# 3_-_Periphery.net
KiCad netlist of a schematic drawn in Altium Designer
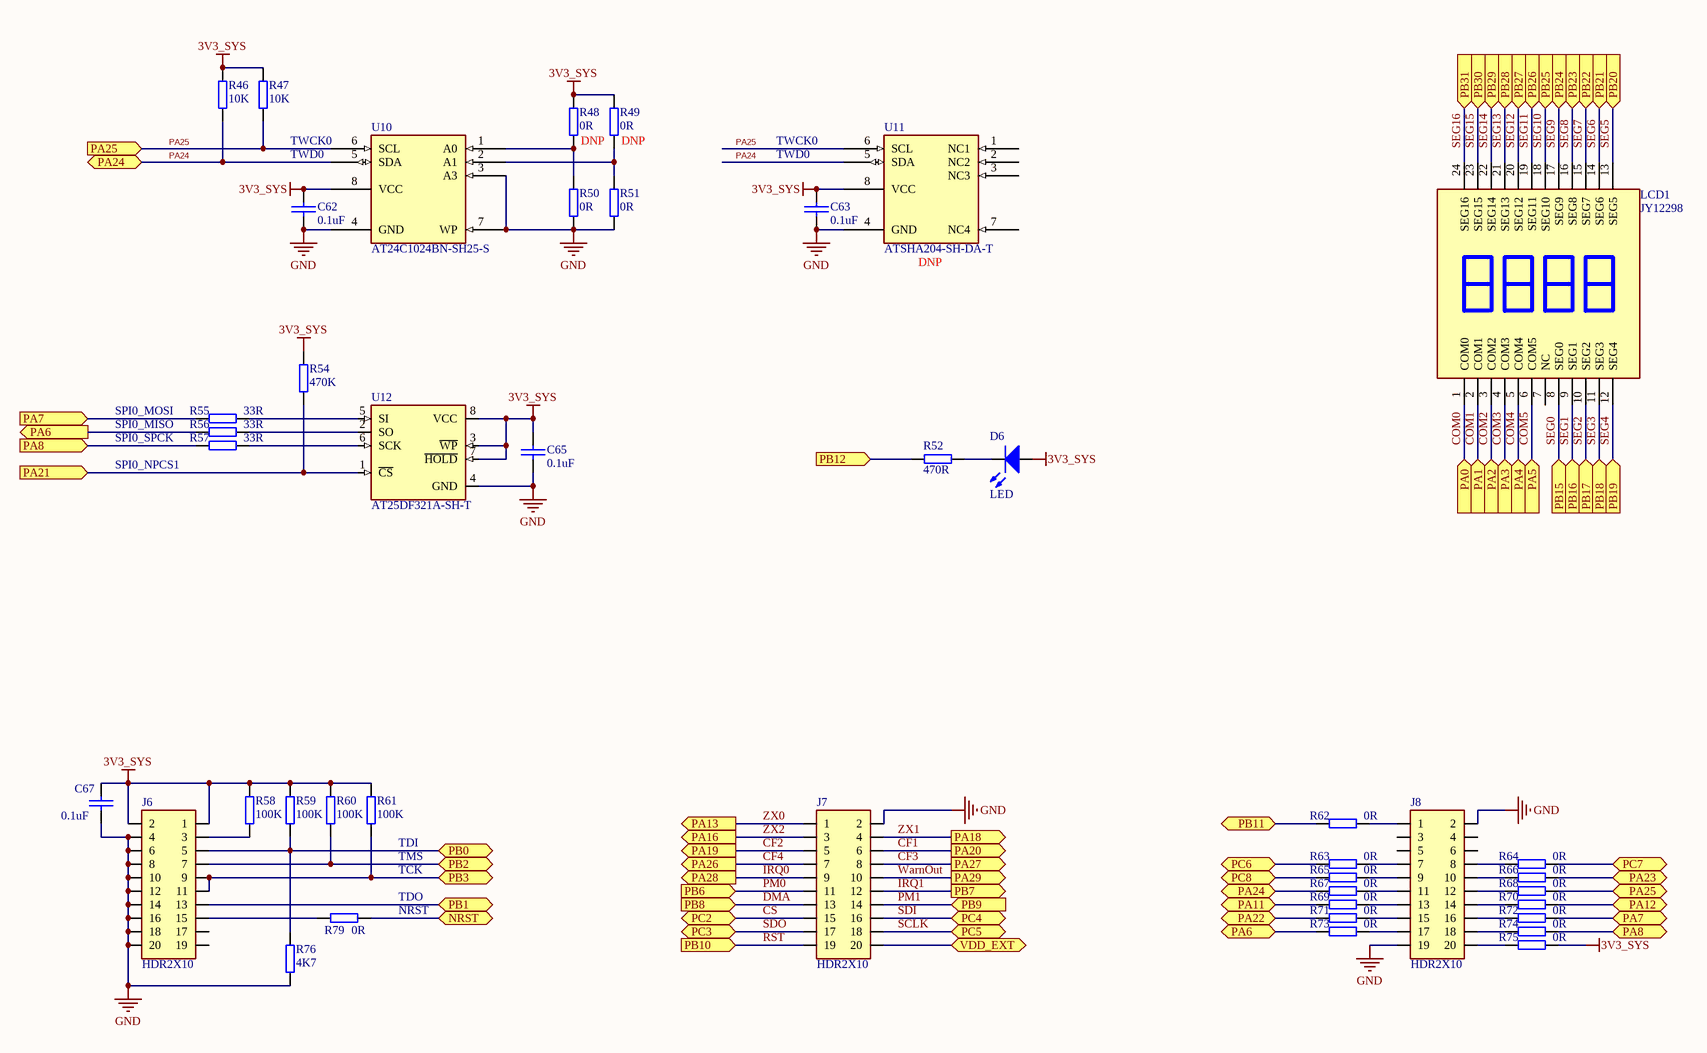
[diagram p0: 3 - Periphery.SchDoc]

(export (version "E")
  (design (tool "Eeschema 10.0.6"))
  (components
    (comp (ref "C62") (value "0.1uF") (footprint "C0603") (libsource (lib "SchLib(AD10)") (part "CAP")))
    (comp (ref "C63") (value "0.1uF") (footprint "C0603") (libsource (lib "SchLib(AD10)") (part "CAP")))
    (comp (ref "C65") (value "0.1uF") (footprint "C0603") (libsource (lib "SchLib(AD10)") (part "CAP")))
    (comp (ref "C67") (value "0.1uF") (footprint "C0603") (libsource (lib "SchLib(AD10)") (part "CAP")))
    (comp (ref "D6") (value "LED") (footprint "LED-0805G") (libsource (lib "SchLib(AD10)") (part "LED")))
    (comp (ref "J6") (value "HDR2X10") (footprint "HDR2X10") (libsource (lib "") (part "HDR2X10_1")))
    (comp (ref "J7")
      (value "HDR2X10")
      (footprint "HDR2X10")
      (libsource (lib "SchLib(AD10)") (part "HDR2X10"))
    )
    (comp (ref "J8")
      (value "HDR2X10")
      (footprint "HDR2X10")
      (libsource (lib "SchLib(AD10)") (part "HDR2X10"))
    )
    (comp (ref "LCD1")
      (value "JY12298")
      (footprint "LCD_JY12298")
      (description "Display,FSTN,Positive,Reflective,JY12298,60.15x45.1mm")
      (fields (field (name "MANUFACTURER") "翼雅"))
      (libsource (lib "SchLib(AD10)") (part "LCD_JY12298"))
    )
    (comp (ref "R46") (value "10K") (footprint "R0603") (libsource (lib "SchLib(AD10)") (part "RES")))
    (comp (ref "R47") (value "10K") (footprint "R0603") (libsource (lib "SchLib(AD10)") (part "RES")))
    (comp (ref "R48") (value "0R") (footprint "R0603") (libsource (lib "SchLib(AD10)") (part "RES")))
    (comp (ref "R49") (value "0R") (footprint "R0603") (libsource (lib "SchLib(AD10)") (part "RES")))
    (comp (ref "R50") (value "0R") (footprint "R0603") (libsource (lib "SchLib(AD10)") (part "RES")))
    (comp (ref "R51") (value "0R") (footprint "R0603") (libsource (lib "SchLib(AD10)") (part "RES")))
    (comp (ref "R52") (value "470R") (footprint "R0603") (libsource (lib "SchLib(AD10)") (part "RES")))
    (comp (ref "R54") (value "470K") (footprint "R0603") (libsource (lib "SchLib(AD10)") (part "RES")))
    (comp (ref "R55") (value "33R") (footprint "R0603") (libsource (lib "SchLib(AD10)") (part "RES")))
    (comp (ref "R56") (value "33R") (footprint "R0603") (libsource (lib "SchLib(AD10)") (part "RES")))
    (comp (ref "R57") (value "33R") (footprint "R0603") (libsource (lib "SchLib(AD10)") (part "RES")))
    (comp (ref "R58") (value "100K") (footprint "R0603") (libsource (lib "SchLib(AD10)") (part "RES")))
    (comp (ref "R59") (value "100K") (footprint "R0603") (libsource (lib "SchLib(AD10)") (part "RES")))
    (comp (ref "R60") (value "100K") (footprint "R0603") (libsource (lib "SchLib(AD10)") (part "RES")))
    (comp (ref "R61") (value "100K") (footprint "R0603") (libsource (lib "SchLib(AD10)") (part "RES")))
    (comp (ref "R62") (value "0R") (footprint "R0603") (libsource (lib "SchLib(AD10)") (part "RES")))
    (comp (ref "R63") (value "0R") (footprint "R0603") (libsource (lib "SchLib(AD10)") (part "RES")))
    (comp (ref "R64") (value "0R") (footprint "R0603") (libsource (lib "SchLib(AD10)") (part "RES")))
    (comp (ref "R65") (value "0R") (footprint "R0603") (libsource (lib "SchLib(AD10)") (part "RES")))
    (comp (ref "R66") (value "0R") (footprint "R0603") (libsource (lib "SchLib(AD10)") (part "RES")))
    (comp (ref "R67") (value "0R") (footprint "R0603") (libsource (lib "SchLib(AD10)") (part "RES")))
    (comp (ref "R68") (value "0R") (footprint "R0603") (libsource (lib "SchLib(AD10)") (part "RES")))
    (comp (ref "R69") (value "0R") (footprint "R0603") (libsource (lib "SchLib(AD10)") (part "RES")))
    (comp (ref "R70") (value "0R") (footprint "R0603") (libsource (lib "SchLib(AD10)") (part "RES")))
    (comp (ref "R71") (value "0R") (footprint "R0603") (libsource (lib "SchLib(AD10)") (part "RES")))
    (comp (ref "R72") (value "0R") (footprint "R0603") (libsource (lib "SchLib(AD10)") (part "RES")))
    (comp (ref "R73") (value "0R") (footprint "R0603") (libsource (lib "SchLib(AD10)") (part "RES")))
    (comp (ref "R74") (value "0R") (footprint "R0603") (libsource (lib "SchLib(AD10)") (part "RES")))
    (comp (ref "R75") (value "0R") (footprint "R0603") (libsource (lib "SchLib(AD10)") (part "RES")))
    (comp (ref "R76") (value "4K7") (footprint "R0603") (libsource (lib "SchLib(AD10)") (part "RES")))
    (comp (ref "R79") (value "0R") (footprint "R0603") (libsource (lib "SchLib(AD10)") (part "RES")))
    (comp (ref "U10")
      (value "AT24C1024BN-SH25-S")
      (footprint "SO8")
      (description "Two Wires Serial EEPROM")
      (fields
        (field (name "MANUFACTURER") "Atmel")
        (field (name "MANUFACTURER PART NUMBER") "AT24C1024BN-SH25")
      )
      (libsource (lib "SchLib(AD10)") (part "AT24C512BN-SH25-SO8_1"))
    )
    (comp (ref "U11")
      (value "ATSHA204-SH-DA-T")
      (footprint "SO8")
      (description "IC,CryptoAuthentication,ATSHA204-SH-DA-T")
      (fields (field (name "MANUFACTURER") "ATMEL"))
      (libsource (lib "SchLib(AD10)") (part "ATSHA204-SH-DA-T"))
    )
    (comp (ref "U12")
      (value "AT25DF321A-SH-T")
      (footprint "SOIC8")
      (description "32 Mb Serial DataFlash")
      (fields (field (name "MANUFACTURER") "ATMEL"))
      (libsource (lib "SchLib(AD10)") (part "AT25DF321_SU"))
    )
  )
  (nets
    (net (code "1") (name "/CF1") (class "Default")
      (node (ref "J7") (pin "6") (pinfunction "6_6") (pintype "passive"))
    )
    (net (code "2") (name "/CF2") (class "Default")
      (node (ref "J7") (pin "5") (pinfunction "5_5") (pintype "passive"))
    )
    (net (code "3") (name "/CF3") (class "Default")
      (node (ref "J7") (pin "8") (pinfunction "8_8") (pintype "passive"))
    )
    (net (code "4") (name "/CF4") (class "Default")
      (node (ref "J7") (pin "7") (pinfunction "7_7") (pintype "passive"))
    )
    (net (code "5") (name "/COM0") (class "Default")
      (node (ref "LCD1") (pin "1") (pinfunction "COM0_1") (pintype "passive"))
    )
    (net (code "6") (name "/COM1") (class "Default")
      (node (ref "LCD1") (pin "2") (pinfunction "COM1_2") (pintype "passive"))
    )
    (net (code "7") (name "/COM2") (class "Default")
      (node (ref "LCD1") (pin "3") (pinfunction "COM2_3") (pintype "passive"))
    )
    (net (code "8") (name "/COM3") (class "Default")
      (node (ref "LCD1") (pin "4") (pinfunction "COM3_4") (pintype "passive"))
    )
    (net (code "9") (name "/COM4") (class "Default")
      (node (ref "LCD1") (pin "5") (pinfunction "COM4_5") (pintype "passive"))
    )
    (net (code "10") (name "/COM5") (class "Default")
      (node (ref "LCD1") (pin "6") (pinfunction "COM5_6") (pintype "passive"))
    )
    (net (code "11") (name "/CS") (class "Default")
      (node (ref "J7") (pin "15") (pinfunction "15_15") (pintype "passive"))
    )
    (net (code "12") (name "/DMA") (class "Default")
      (node (ref "J7") (pin "13") (pinfunction "13_13") (pintype "passive"))
    )
    (net (code "13") (name "/IRQ0") (class "Default")
      (node (ref "J7") (pin "9") (pinfunction "9_9") (pintype "passive"))
    )
    (net (code "14") (name "/IRQ1") (class "Default")
      (node (ref "J7") (pin "12") (pinfunction "12_12") (pintype "passive"))
    )
    (net (code "15") (name "/NRST") (class "Default")
      (node (ref "R79") (pin "2") (pinfunction "2_2") (pintype "passive"))
    )
    (net (code "16") (name "/PA6") (class "Default")
      (node (ref "R56") (pin "1") (pinfunction "1_1") (pintype "passive"))
      (node (ref "R73") (pin "1") (pinfunction "1_1") (pintype "passive"))
    )
    (net (code "17") (name "/PA7") (class "Default")
      (node (ref "R55") (pin "1") (pinfunction "1_1") (pintype "passive"))
      (node (ref "R72") (pin "2") (pinfunction "2_2") (pintype "passive"))
    )
    (net (code "18") (name "/PA8") (class "Default")
      (node (ref "R57") (pin "1") (pinfunction "1_1") (pintype "passive"))
      (node (ref "R74") (pin "2") (pinfunction "2_2") (pintype "passive"))
    )
    (net (code "19") (name "/PA11") (class "Default")
      (node (ref "R69") (pin "1") (pinfunction "1_1") (pintype "passive"))
    )
    (net (code "20") (name "/PA12") (class "Default")
      (node (ref "R70") (pin "2") (pinfunction "2_2") (pintype "passive"))
    )
    (net (code "21") (name "/PA21") (class "Default")
      (node (ref "R54") (pin "1") (pinfunction "1_1") (pintype "passive"))
      (node (ref "U12") (pin "1") (pinfunction "~{CS}_1") (pintype "input"))
    )
    (net (code "22") (name "/PA22") (class "Default")
      (node (ref "R71") (pin "1") (pinfunction "1_1") (pintype "passive"))
    )
    (net (code "23") (name "/PA23") (class "Default")
      (node (ref "R66") (pin "2") (pinfunction "2_2") (pintype "passive"))
    )
    (net (code "24") (name "/PA24") (class "Default")
      (node (ref "R46") (pin "1") (pinfunction "1_1") (pintype "passive"))
      (node (ref "R67") (pin "1") (pinfunction "1_1") (pintype "passive"))
      (node (ref "U10") (pin "5") (pinfunction "SDA_5") (pintype "bidirectional"))
      (node (ref "U11") (pin "5") (pinfunction "SDA_5") (pintype "bidirectional"))
    )
    (net (code "25") (name "/PA25") (class "Default")
      (node (ref "R47") (pin "1") (pinfunction "1_1") (pintype "passive"))
      (node (ref "R68") (pin "2") (pinfunction "2_2") (pintype "passive"))
      (node (ref "U10") (pin "6") (pinfunction "SCL_6") (pintype "input"))
      (node (ref "U11") (pin "6") (pinfunction "SCL_6") (pintype "input"))
    )
    (net (code "26") (name "/PB0") (class "Default")
      (node (ref "J6") (pin "5") (pinfunction "5_5") (pintype "passive"))
      (node (ref "R59") (pin "1") (pinfunction "1_1") (pintype "passive"))
      (node (ref "R76") (pin "2") (pinfunction "2_2") (pintype "passive"))
    )
    (net (code "27") (name "/PB1") (class "Default")
      (node (ref "J6") (pin "13") (pinfunction "13_13") (pintype "passive"))
    )
    (net (code "28") (name "/PB2") (class "Default")
      (node (ref "J6") (pin "7") (pinfunction "7_7") (pintype "passive"))
      (node (ref "R60") (pin "1") (pinfunction "1_1") (pintype "passive"))
    )
    (net (code "29") (name "/PB3") (class "Default")
      (node (ref "J6") (pin "11") (pinfunction "11_11") (pintype "passive"))
      (node (ref "J6") (pin "9") (pinfunction "9_9") (pintype "passive"))
      (node (ref "R61") (pin "1") (pinfunction "1_1") (pintype "passive"))
    )
    (net (code "30") (name "/PB11") (class "Default")
      (node (ref "R62") (pin "1") (pinfunction "1_1") (pintype "passive"))
    )
    (net (code "31") (name "/PB12") (class "Default")
      (node (ref "R52") (pin "1") (pinfunction "1_1") (pintype "passive"))
    )
    (net (code "32") (name "/PC6") (class "Default")
      (node (ref "R63") (pin "1") (pinfunction "1_1") (pintype "passive"))
    )
    (net (code "33") (name "/PC7") (class "Default")
      (node (ref "R64") (pin "2") (pinfunction "2_2") (pintype "passive"))
    )
    (net (code "34") (name "/PC8") (class "Default")
      (node (ref "R65") (pin "1") (pinfunction "1_1") (pintype "passive"))
    )
    (net (code "35") (name "/PM0") (class "Default")
      (node (ref "J7") (pin "11") (pinfunction "11_11") (pintype "passive"))
    )
    (net (code "36") (name "/PM1") (class "Default")
      (node (ref "J7") (pin "14") (pinfunction "14_14") (pintype "passive"))
    )
    (net (code "37") (name "/RST") (class "Default")
      (node (ref "J7") (pin "19") (pinfunction "19_19") (pintype "passive"))
    )
    (net (code "38") (name "/SCLK") (class "Default")
      (node (ref "J7") (pin "18") (pinfunction "18_18") (pintype "passive"))
    )
    (net (code "39") (name "/SDI") (class "Default")
      (node (ref "J7") (pin "16") (pinfunction "16_16") (pintype "passive"))
    )
    (net (code "40") (name "/SDO") (class "Default")
      (node (ref "J7") (pin "17") (pinfunction "17_17") (pintype "passive"))
    )
    (net (code "41") (name "/SEG0") (class "Default")
      (node (ref "LCD1") (pin "8") (pinfunction "SEG0_8") (pintype "passive"))
    )
    (net (code "42") (name "/SEG1") (class "Default")
      (node (ref "LCD1") (pin "9") (pinfunction "SEG1_9") (pintype "passive"))
    )
    (net (code "43") (name "/SEG2") (class "Default")
      (node (ref "LCD1") (pin "10") (pinfunction "SEG2_10") (pintype "passive"))
    )
    (net (code "44") (name "/SEG3") (class "Default")
      (node (ref "LCD1") (pin "11") (pinfunction "SEG3_11") (pintype "passive"))
    )
    (net (code "45") (name "/SEG4") (class "Default")
      (node (ref "LCD1") (pin "12") (pinfunction "SEG4_12") (pintype "passive"))
    )
    (net (code "46") (name "/SEG5") (class "Default")
      (node (ref "LCD1") (pin "13") (pinfunction "SEG5_13") (pintype "passive"))
    )
    (net (code "47") (name "/SEG6") (class "Default")
      (node (ref "LCD1") (pin "14") (pinfunction "SEG6_14") (pintype "passive"))
    )
    (net (code "48") (name "/SEG7") (class "Default")
      (node (ref "LCD1") (pin "15") (pinfunction "SEG7_15") (pintype "passive"))
    )
    (net (code "49") (name "/SEG8") (class "Default")
      (node (ref "LCD1") (pin "16") (pinfunction "SEG8_16") (pintype "passive"))
    )
    (net (code "50") (name "/SEG9") (class "Default")
      (node (ref "LCD1") (pin "17") (pinfunction "SEG9_17") (pintype "passive"))
    )
    (net (code "51") (name "/SEG10") (class "Default")
      (node (ref "LCD1") (pin "18") (pinfunction "SEG10_18") (pintype "passive"))
    )
    (net (code "52") (name "/SEG11") (class "Default")
      (node (ref "LCD1") (pin "19") (pinfunction "SEG11_19") (pintype "passive"))
    )
    (net (code "53") (name "/SEG12") (class "Default")
      (node (ref "LCD1") (pin "20") (pinfunction "SEG12_20") (pintype "passive"))
    )
    (net (code "54") (name "/SEG13") (class "Default")
      (node (ref "LCD1") (pin "21") (pinfunction "SEG13_21") (pintype "passive"))
    )
    (net (code "55") (name "/SEG14") (class "Default")
      (node (ref "LCD1") (pin "22") (pinfunction "SEG14_22") (pintype "passive"))
    )
    (net (code "56") (name "/SEG15") (class "Default")
      (node (ref "LCD1") (pin "23") (pinfunction "SEG15_23") (pintype "passive"))
    )
    (net (code "57") (name "/SEG16") (class "Default")
      (node (ref "LCD1") (pin "24") (pinfunction "SEG16_24") (pintype "passive"))
    )
    (net (code "58") (name "/VDD_EXT") (class "Default")
      (node (ref "J7") (pin "20") (pinfunction "20_20") (pintype "passive"))
    )
    (net (code "59") (name "/WarnOut") (class "Default")
      (node (ref "J7") (pin "10") (pinfunction "10_10") (pintype "passive"))
    )
    (net (code "60") (name "/ZX0") (class "Default")
      (node (ref "J7") (pin "1") (pinfunction "1_1") (pintype "passive"))
    )
    (net (code "61") (name "/ZX1") (class "Default")
      (node (ref "J7") (pin "4") (pinfunction "4_4") (pintype "passive"))
    )
    (net (code "62") (name "/ZX2") (class "Default")
      (node (ref "J7") (pin "3") (pinfunction "3_3") (pintype "passive"))
    )
    (net (code "63") (name "3V3_SYS") (class "Default")
      (node (ref "C62") (pin "2") (pintype "passive"))
      (node (ref "C63") (pin "2") (pintype "passive"))
      (node (ref "C65") (pin "2") (pintype "passive"))
      (node (ref "C67") (pin "2") (pintype "passive"))
      (node (ref "D6") (pin "A") (pinfunction "A_A") (pintype "passive"))
      (node (ref "J6") (pin "1") (pinfunction "1_1") (pintype "passive"))
      (node (ref "J6") (pin "2") (pinfunction "2_2") (pintype "passive"))
      (node (ref "R46") (pin "2") (pinfunction "2_2") (pintype "passive"))
      (node (ref "R47") (pin "2") (pinfunction "2_2") (pintype "passive"))
      (node (ref "R48") (pin "2") (pinfunction "2_2") (pintype "passive"))
      (node (ref "R49") (pin "2") (pinfunction "2_2") (pintype "passive"))
      (node (ref "R54") (pin "2") (pinfunction "2_2") (pintype "passive"))
      (node (ref "R58") (pin "2") (pinfunction "2_2") (pintype "passive"))
      (node (ref "R59") (pin "2") (pinfunction "2_2") (pintype "passive"))
      (node (ref "R60") (pin "2") (pinfunction "2_2") (pintype "passive"))
      (node (ref "R61") (pin "2") (pinfunction "2_2") (pintype "passive"))
      (node (ref "R75") (pin "2") (pinfunction "2_2") (pintype "passive"))
      (node (ref "U10") (pin "8") (pinfunction "VCC_8") (pintype "power_in"))
      (node (ref "U11") (pin "8") (pinfunction "VCC_8") (pintype "power_in"))
      (node (ref "U12") (pin "3") (pinfunction "~{WP}_3") (pintype "input"))
      (node (ref "U12") (pin "7") (pinfunction "~{HOLD}_7") (pintype "input"))
      (node (ref "U12") (pin "8") (pinfunction "VCC_8") (pintype "power_in"))
    )
    (net (code "64") (name "GND") (class "Default")
      (node (ref "C62") (pin "1") (pintype "passive"))
      (node (ref "C63") (pin "1") (pintype "passive"))
      (node (ref "C65") (pin "1") (pintype "passive"))
      (node (ref "C67") (pin "1") (pintype "passive"))
      (node (ref "J6") (pin "10") (pinfunction "10_10") (pintype "passive"))
      (node (ref "J6") (pin "12") (pinfunction "12_12") (pintype "passive"))
      (node (ref "J6") (pin "14") (pinfunction "14_14") (pintype "passive"))
      (node (ref "J6") (pin "16") (pinfunction "16_16") (pintype "passive"))
      (node (ref "J6") (pin "18") (pinfunction "18_18") (pintype "passive"))
      (node (ref "J6") (pin "20") (pinfunction "20_20") (pintype "passive"))
      (node (ref "J6") (pin "4") (pinfunction "4_4") (pintype "passive"))
      (node (ref "J6") (pin "6") (pinfunction "6_6") (pintype "passive"))
      (node (ref "J6") (pin "8") (pinfunction "8_8") (pintype "passive"))
      (node (ref "J7") (pin "2") (pinfunction "2_2") (pintype "passive"))
      (node (ref "J8") (pin "19") (pinfunction "19_19") (pintype "passive"))
      (node (ref "J8") (pin "2") (pinfunction "2_2") (pintype "passive"))
      (node (ref "R50") (pin "1") (pinfunction "1_1") (pintype "passive"))
      (node (ref "R51") (pin "1") (pinfunction "1_1") (pintype "passive"))
      (node (ref "R76") (pin "1") (pinfunction "1_1") (pintype "passive"))
      (node (ref "U10") (pin "3") (pinfunction "A3_3") (pintype "input"))
      (node (ref "U10") (pin "4") (pinfunction "GND_4") (pintype "power_in"))
      (node (ref "U10") (pin "7") (pinfunction "WP_7") (pintype "input"))
      (node (ref "U11") (pin "4") (pinfunction "GND_4") (pintype "power_in"))
      (node (ref "U12") (pin "4") (pinfunction "GND_4") (pintype "power_in"))
    )
    (net (code "65") (name "Net-(D6-PadK)") (class "Default")
      (node (ref "D6") (pin "K") (pinfunction "K_K") (pintype "passive"))
      (node (ref "R52") (pin "2") (pinfunction "2_2") (pintype "passive"))
    )
    (net (code "66") (name "Net-(J6-Pad3)") (class "Default")
      (node (ref "J6") (pin "3") (pinfunction "3_3") (pintype "passive"))
      (node (ref "R58") (pin "1") (pinfunction "1_1") (pintype "passive"))
    )
    (net (code "67") (name "Net-(J6-Pad15)") (class "Default")
      (node (ref "J6") (pin "15") (pinfunction "15_15") (pintype "passive"))
      (node (ref "R79") (pin "1") (pinfunction "1_1") (pintype "passive"))
    )
    (net (code "68") (name "Net-(J8-Pad1)") (class "Default")
      (node (ref "J8") (pin "1") (pinfunction "1_1") (pintype "passive"))
      (node (ref "R62") (pin "2") (pinfunction "2_2") (pintype "passive"))
    )
    (net (code "69") (name "Net-(J8-Pad7)") (class "Default")
      (node (ref "J8") (pin "7") (pinfunction "7_7") (pintype "passive"))
      (node (ref "R63") (pin "2") (pinfunction "2_2") (pintype "passive"))
    )
    (net (code "70") (name "Net-(J8-Pad8)") (class "Default")
      (node (ref "J8") (pin "8") (pinfunction "8_8") (pintype "passive"))
      (node (ref "R64") (pin "1") (pinfunction "1_1") (pintype "passive"))
    )
    (net (code "71") (name "Net-(J8-Pad9)") (class "Default")
      (node (ref "J8") (pin "9") (pinfunction "9_9") (pintype "passive"))
      (node (ref "R65") (pin "2") (pinfunction "2_2") (pintype "passive"))
    )
    (net (code "72") (name "Net-(J8-Pad10)") (class "Default")
      (node (ref "J8") (pin "10") (pinfunction "10_10") (pintype "passive"))
      (node (ref "R66") (pin "1") (pinfunction "1_1") (pintype "passive"))
    )
    (net (code "73") (name "Net-(J8-Pad11)") (class "Default")
      (node (ref "J8") (pin "11") (pinfunction "11_11") (pintype "passive"))
      (node (ref "R67") (pin "2") (pinfunction "2_2") (pintype "passive"))
    )
    (net (code "74") (name "Net-(J8-Pad12)") (class "Default")
      (node (ref "J8") (pin "12") (pinfunction "12_12") (pintype "passive"))
      (node (ref "R68") (pin "1") (pinfunction "1_1") (pintype "passive"))
    )
    (net (code "75") (name "Net-(J8-Pad13)") (class "Default")
      (node (ref "J8") (pin "13") (pinfunction "13_13") (pintype "passive"))
      (node (ref "R69") (pin "2") (pinfunction "2_2") (pintype "passive"))
    )
    (net (code "76") (name "Net-(J8-Pad14)") (class "Default")
      (node (ref "J8") (pin "14") (pinfunction "14_14") (pintype "passive"))
      (node (ref "R70") (pin "1") (pinfunction "1_1") (pintype "passive"))
    )
    (net (code "77") (name "Net-(J8-Pad15)") (class "Default")
      (node (ref "J8") (pin "15") (pinfunction "15_15") (pintype "passive"))
      (node (ref "R71") (pin "2") (pinfunction "2_2") (pintype "passive"))
    )
    (net (code "78") (name "Net-(J8-Pad16)") (class "Default")
      (node (ref "J8") (pin "16") (pinfunction "16_16") (pintype "passive"))
      (node (ref "R72") (pin "1") (pinfunction "1_1") (pintype "passive"))
    )
    (net (code "79") (name "Net-(J8-Pad17)") (class "Default")
      (node (ref "J8") (pin "17") (pinfunction "17_17") (pintype "passive"))
      (node (ref "R73") (pin "2") (pinfunction "2_2") (pintype "passive"))
    )
    (net (code "80") (name "Net-(J8-Pad18)") (class "Default")
      (node (ref "J8") (pin "18") (pinfunction "18_18") (pintype "passive"))
      (node (ref "R74") (pin "1") (pinfunction "1_1") (pintype "passive"))
    )
    (net (code "81") (name "Net-(J8-Pad20)") (class "Default")
      (node (ref "J8") (pin "20") (pinfunction "20_20") (pintype "passive"))
      (node (ref "R75") (pin "1") (pinfunction "1_1") (pintype "passive"))
    )
    (net (code "82") (name "Net-(U10-A0)") (class "Default")
      (node (ref "R48") (pin "1") (pinfunction "1_1") (pintype "passive"))
      (node (ref "R50") (pin "2") (pinfunction "2_2") (pintype "passive"))
      (node (ref "U10") (pin "1") (pinfunction "A0_1") (pintype "input"))
    )
    (net (code "83") (name "Net-(U10-A1)") (class "Default")
      (node (ref "R49") (pin "1") (pinfunction "1_1") (pintype "passive"))
      (node (ref "R51") (pin "2") (pinfunction "2_2") (pintype "passive"))
      (node (ref "U10") (pin "2") (pinfunction "A1_2") (pintype "input"))
    )
    (net (code "84") (name "Net-(U12-SCK)") (class "Default")
      (node (ref "R57") (pin "2") (pinfunction "2_2") (pintype "passive"))
      (node (ref "U12") (pin "6") (pinfunction "SCK_6") (pintype "input"))
    )
    (net (code "85") (name "Net-(U12-SI)") (class "Default")
      (node (ref "R55") (pin "2") (pinfunction "2_2") (pintype "passive"))
      (node (ref "U12") (pin "5") (pinfunction "SI_5") (pintype "input"))
    )
    (net (code "86") (name "Net-(U12-SO)") (class "Default")
      (node (ref "R56") (pin "2") (pinfunction "2_2") (pintype "passive"))
      (node (ref "U12") (pin "2") (pinfunction "SO_2") (pintype "tri_state"))
    )
    (net (code "87") (name "unconnected-(J6-Pad17)") (class "Default")
      (node (ref "J6") (pin "17") (pinfunction "17_17") (pintype "passive"))
    )
    (net (code "88") (name "unconnected-(J6-Pad19)") (class "Default")
      (node (ref "J6") (pin "19") (pinfunction "19_19") (pintype "passive"))
    )
    (net (code "89") (name "unconnected-(J8-Pad3)") (class "Default")
      (node (ref "J8") (pin "3") (pinfunction "3_3") (pintype "passive"))
    )
    (net (code "90") (name "unconnected-(J8-Pad4)") (class "Default")
      (node (ref "J8") (pin "4") (pinfunction "4_4") (pintype "passive"))
    )
    (net (code "91") (name "unconnected-(J8-Pad5)") (class "Default")
      (node (ref "J8") (pin "5") (pinfunction "5_5") (pintype "passive"))
    )
    (net (code "92") (name "unconnected-(J8-Pad6)") (class "Default")
      (node (ref "J8") (pin "6") (pinfunction "6_6") (pintype "passive"))
    )
    (net (code "93") (name "unconnected-(LCD1-NC-Pad7)") (class "Default")
      (node (ref "LCD1") (pin "7") (pinfunction "NC_7") (pintype "passive"))
    )
    (net (code "94") (name "unconnected-(U11-NC1-Pad1)") (class "Default")
      (node (ref "U11") (pin "1") (pinfunction "NC1_1") (pintype "input"))
    )
    (net (code "95") (name "unconnected-(U11-NC2-Pad2)") (class "Default")
      (node (ref "U11") (pin "2") (pinfunction "NC2_2") (pintype "input"))
    )
    (net (code "96") (name "unconnected-(U11-NC3-Pad3)") (class "Default")
      (node (ref "U11") (pin "3") (pinfunction "NC3_3") (pintype "input"))
    )
    (net (code "97") (name "unconnected-(U11-NC4-Pad7)") (class "Default")
      (node (ref "U11") (pin "7") (pinfunction "NC4_7") (pintype "input"))
    )
  )
)
